# LPS22HBTR.net
KiCad netlist of a schematic drawn in Altium Designer
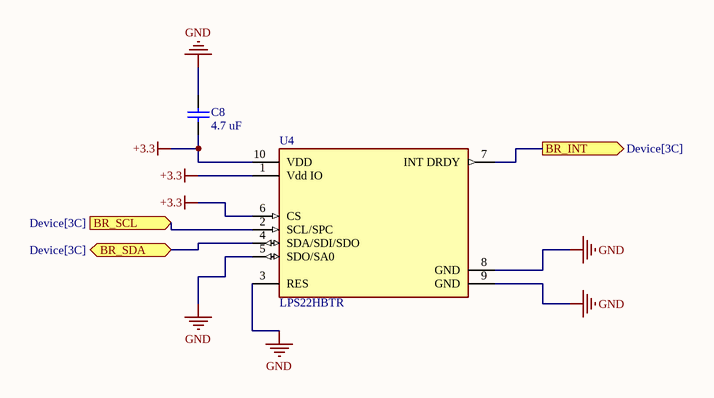
[diagram p0: LPS22HBTR.SchDoc]

(export (version "E")
  (design (tool "Eeschema 10.0.6"))
  (components
    (comp (ref "C8")
      (value "4.7 uF")
      (footprint "CAPC1005X55X25NL05T10")
      (fields (field (name "MANUFACTURER") "Murata") (field (name "PART NUMBER") "GRM155F50J684ZE01D"))
      (libsource (lib "Altium Content Vault") (part "CAP"))
    )
    (comp (ref "U4")
      (value "LPS22HBTR")
      (footprint "FP-HLGA-10L-8479831-0")
      (description "MEMS NANO PRESSURE SENSOR: 260-1")
      (fields
        (field (name "OCTOPART") "https://octopart.com/lps22hbtr-stmicroelectronics-51851131")
        (field (name "MANUFACTURER") "STMicroelectronics")
      )
      (libsource (lib "Altium Content Vault") (part "d4c28707ea3ba579869663dd93796c5"))
    )
  )
  (nets
    (net (code "1") (name "+3.3") (class "Default")
      (node (ref "C8") (pin "2") (pinfunction "2_2") (pintype "passive"))
      (node (ref "U4") (pin "1") (pinfunction "Vdd_IO_1") (pintype "power_in"))
      (node (ref "U4") (pin "10") (pinfunction "VDD_10") (pintype "power_in"))
      (node (ref "U4") (pin "6") (pinfunction "CS_6") (pintype "input"))
    )
    (net (code "2") (name "/BR_INT") (class "Default")
      (node (ref "U4") (pin "7") (pinfunction "INT_DRDY_7") (pintype "output"))
    )
    (net (code "3") (name "/BR_SCL") (class "Default")
      (node (ref "U4") (pin "2") (pinfunction "SCL/SPC_2") (pintype "input"))
    )
    (net (code "4") (name "/BR_SDA") (class "Default")
      (node (ref "U4") (pin "4") (pinfunction "SDA/SDI/SDO_4") (pintype "bidirectional"))
    )
    (net (code "5") (name "GND") (class "Default")
      (node (ref "C8") (pin "1") (pinfunction "1_1") (pintype "passive"))
      (node (ref "U4") (pin "3") (pinfunction "RES_3") (pintype "passive"))
      (node (ref "U4") (pin "5") (pinfunction "SDO/SA0_5") (pintype "bidirectional"))
      (node (ref "U4") (pin "8") (pinfunction "GND_8") (pintype "power_in"))
      (node (ref "U4") (pin "9") (pinfunction "GND_9") (pintype "power_in"))
    )
  )
)
